# LINLCDV2.net
KiCad netlist of a schematic drawn in EAGLE
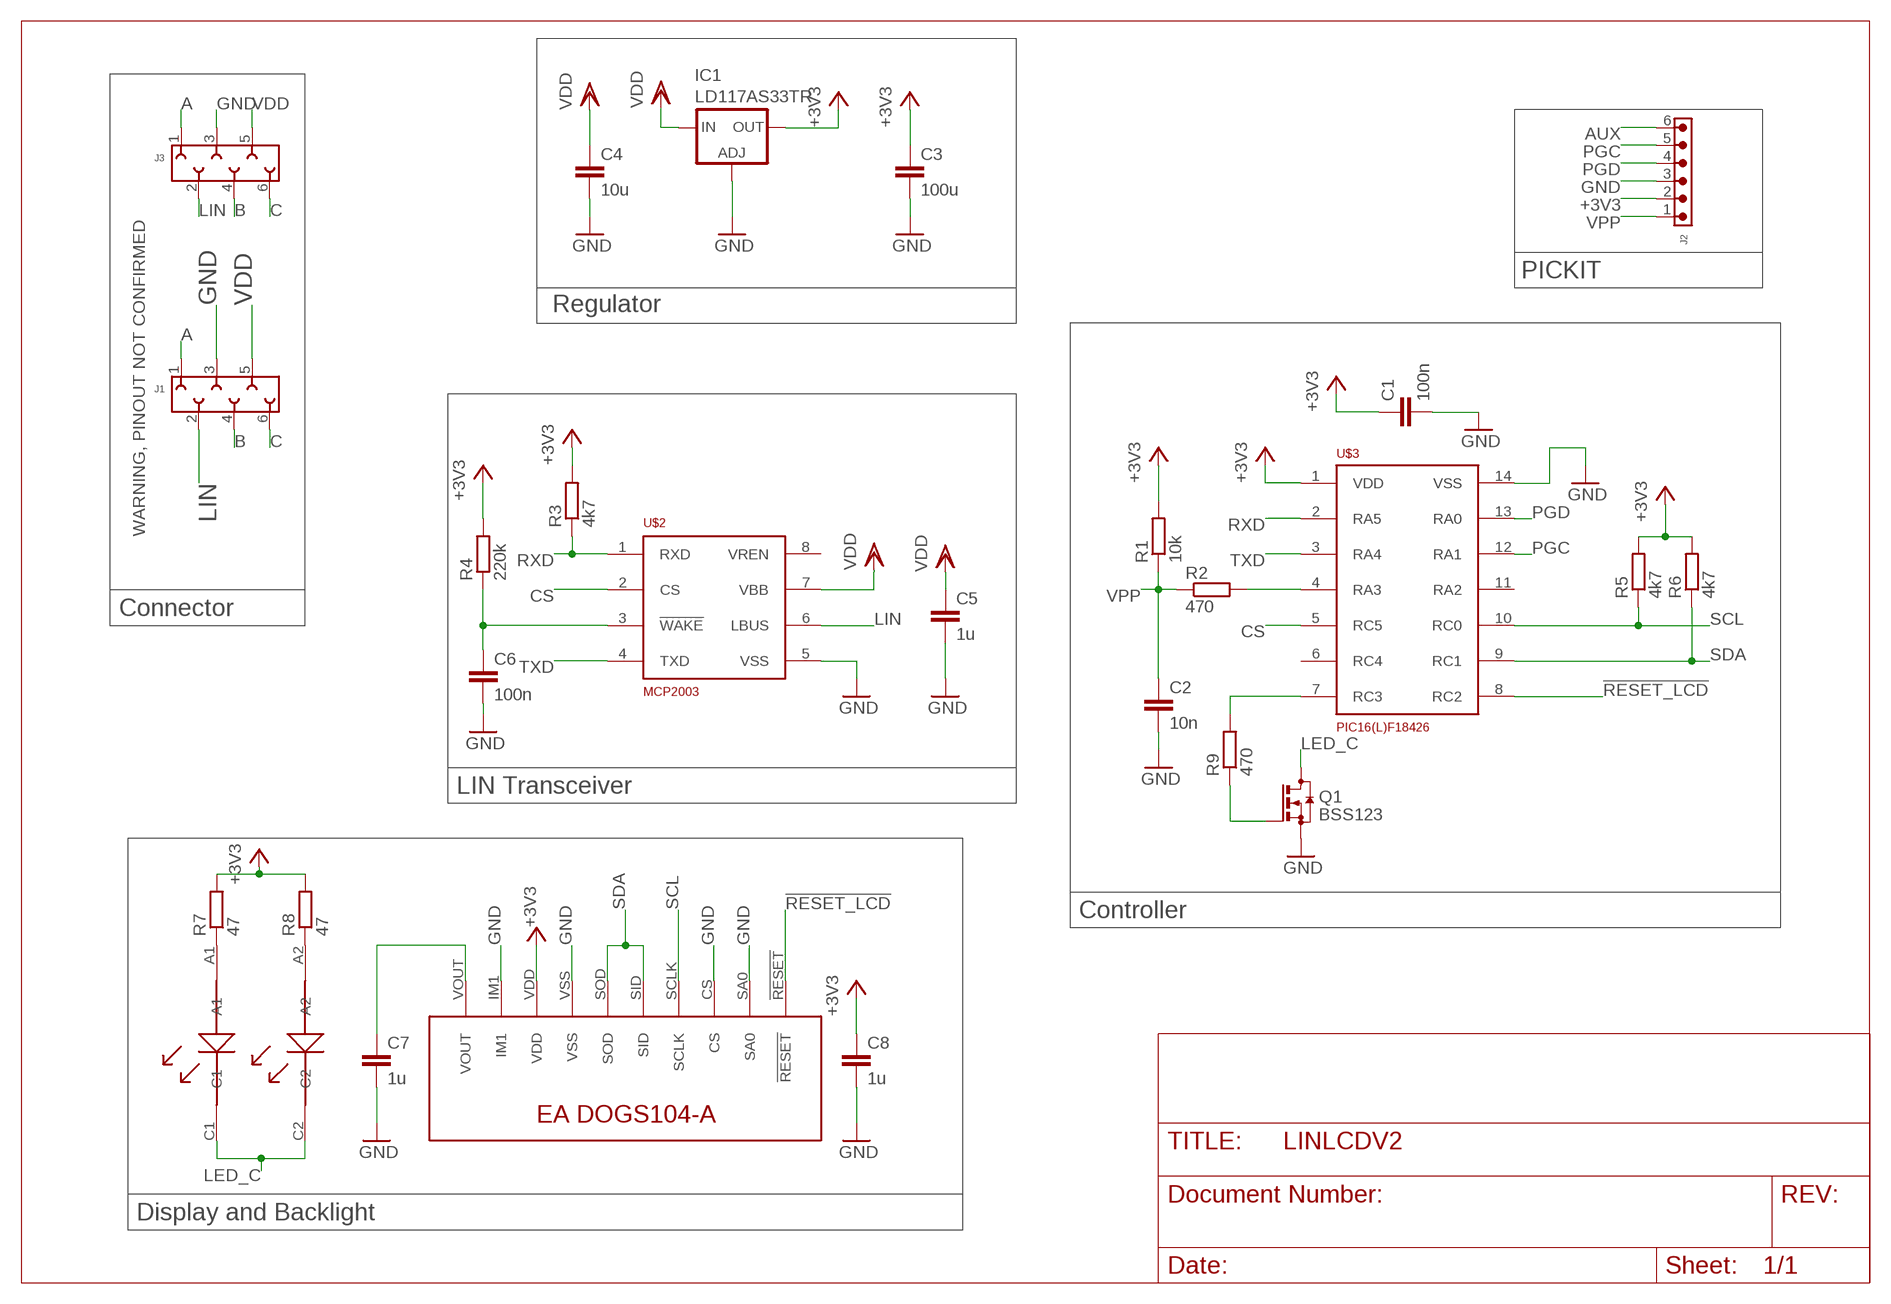
[diagram p0: schematic, sheet 1]

(export (version "E")
  (design (tool "Eeschema 10.0.6"))
  (components
    (comp (ref "C1")
      (value "100n")
      (footprint "eagle-import:C0603")
      (libsource (lib "eagle-import") (part "C-EUC0603"))
    )
    (comp (ref "C2")
      (value "10n")
      (footprint "eagle-import:C0603")
      (libsource (lib "eagle-import") (part "C-EUC0603"))
    )
    (comp (ref "C3")
      (value "100u")
      (footprint "eagle-import:C1206")
      (libsource (lib "eagle-import") (part "C-EUC1206"))
    )
    (comp (ref "C4")
      (value "10u")
      (footprint "eagle-import:C1206")
      (libsource (lib "eagle-import") (part "C-EUC1206"))
    )
    (comp (ref "C5")
      (value "1u")
      (footprint "eagle-import:C1206")
      (libsource (lib "eagle-import") (part "C-EUC1206"))
    )
    (comp (ref "C6")
      (value "100n")
      (footprint "eagle-import:C0603")
      (libsource (lib "eagle-import") (part "C-EUC0603"))
    )
    (comp (ref "C7")
      (value "1u")
      (footprint "eagle-import:C1206")
      (libsource (lib "eagle-import") (part "C-EUC1206"))
    )
    (comp (ref "C8")
      (value "1u")
      (footprint "eagle-import:C1206")
      (libsource (lib "eagle-import") (part "C-EUC1206"))
    )
    (comp (ref "IC1")
      (value "LD117AS33TR")
      (footprint "eagle-import:SOT223")
      (libsource (lib "eagle-import") (part "LD117A?S33TR"))
    )
    (comp (ref "J1")
      (value "690367280676")
      (footprint "eagle-import:690367280676")
      (libsource (lib "eagle-import") (part "690367280676"))
    )
    (comp (ref "J2")
      (value "6130XX11021_61300611021")
      (footprint "eagle-import:61300611021")
      (libsource (lib "eagle-import") (part "6130XX11021_61300611021"))
    )
    (comp (ref "J3")
      (value "690367280676")
      (footprint "eagle-import:690367280676")
      (libsource (lib "eagle-import") (part "690367280676"))
    )
    (comp (ref "Q1")
      (value "BSS123")
      (footprint "eagle-import:SOT23")
      (libsource (lib "eagle-import") (part "BSS123"))
    )
    (comp (ref "R1")
      (value "10k")
      (footprint "eagle-import:R0603")
      (libsource (lib "eagle-import") (part "R-EU_R0603"))
    )
    (comp (ref "R2")
      (value "470")
      (footprint "eagle-import:R0603")
      (libsource (lib "eagle-import") (part "R-EU_R0603"))
    )
    (comp (ref "R3")
      (value "4k7")
      (footprint "eagle-import:R0603")
      (libsource (lib "eagle-import") (part "R-EU_R0603"))
    )
    (comp (ref "R4")
      (value "220k")
      (footprint "eagle-import:R0603")
      (libsource (lib "eagle-import") (part "R-EU_R0603"))
    )
    (comp (ref "R5")
      (value "4k7")
      (footprint "eagle-import:R0603")
      (libsource (lib "eagle-import") (part "R-EU_R0603"))
    )
    (comp (ref "R6")
      (value "4k7")
      (footprint "eagle-import:R0603")
      (libsource (lib "eagle-import") (part "R-EU_R0603"))
    )
    (comp (ref "R7")
      (value "47")
      (footprint "eagle-import:R0603")
      (libsource (lib "eagle-import") (part "R-EU_R0603"))
    )
    (comp (ref "R8")
      (value "47")
      (footprint "eagle-import:R0603")
      (libsource (lib "eagle-import") (part "R-EU_R0603"))
    )
    (comp (ref "R9")
      (value "470")
      (footprint "eagle-import:R0603")
      (libsource (lib "eagle-import") (part "R-EU_R0603"))
    )
    (comp (ref "U$1")
      (value "DOGS104-A")
      (footprint "eagle-import:DOGS104-A")
      (libsource (lib "eagle-import") (part "DOGS104-A"))
    )
    (comp (ref "U$2")
      (value "MCP2003")
      (footprint "eagle-import:SO-08")
      (libsource (lib "eagle-import") (part "MCP2003"))
    )
    (comp (ref "U$3")
      (value "PIC16(L)F18426")
      (footprint "eagle-import:SO-14")
      (libsource (lib "eagle-import") (part "PIC16(L)F18426"))
    )
  )
  (nets
    (net (code "1") (name "+3V3") (class "Default")
      (node (ref "C1") (pin "1") (pinfunction "1_1") (pintype "passive"))
      (node (ref "C3") (pin "1") (pinfunction "1_1") (pintype "passive"))
      (node (ref "C8") (pin "1") (pinfunction "1_1") (pintype "passive"))
      (node (ref "IC1") (pin "4") (pinfunction "OUT_4") (pintype "passive"))
      (node (ref "J2") (pin "2") (pinfunction "2_2") (pintype "passive"))
      (node (ref "R1") (pin "2") (pinfunction "2_2") (pintype "passive"))
      (node (ref "R3") (pin "2") (pinfunction "2_2") (pintype "passive"))
      (node (ref "R4") (pin "2") (pinfunction "2_2") (pintype "passive"))
      (node (ref "R5") (pin "2") (pinfunction "2_2") (pintype "passive"))
      (node (ref "R6") (pin "2") (pinfunction "2_2") (pintype "passive"))
      (node (ref "R7") (pin "2") (pinfunction "2_2") (pintype "passive"))
      (node (ref "R8") (pin "2") (pinfunction "2_2") (pintype "passive"))
      (node (ref "U$1") (pin "VDD") (pinfunction "VDD_VDD") (pintype "bidirectional"))
      (node (ref "U$3") (pin "1") (pinfunction "VDD_1") (pintype "bidirectional"))
    )
    (net (code "2") (name "/A") (class "Default")
      (node (ref "J1") (pin "1") (pinfunction "1_1") (pintype "passive"))
      (node (ref "J3") (pin "1") (pinfunction "1_1") (pintype "passive"))
    )
    (net (code "3") (name "/AUX") (class "Default")
      (node (ref "J2") (pin "6") (pinfunction "6_6") (pintype "passive"))
    )
    (net (code "4") (name "/B") (class "Default")
      (node (ref "J1") (pin "4") (pinfunction "4_4") (pintype "passive"))
      (node (ref "J3") (pin "4") (pinfunction "4_4") (pintype "passive"))
    )
    (net (code "5") (name "/C") (class "Default")
      (node (ref "J1") (pin "6") (pinfunction "6_6") (pintype "passive"))
      (node (ref "J3") (pin "6") (pinfunction "6_6") (pintype "passive"))
    )
    (net (code "6") (name "/CS") (class "Default")
      (node (ref "U$2") (pin "2") (pinfunction "CS_2") (pintype "bidirectional"))
      (node (ref "U$3") (pin "5") (pinfunction "RC5_5") (pintype "bidirectional"))
    )
    (net (code "7") (name "/LED_C") (class "Default")
      (node (ref "Q1") (pin "3") (pinfunction "D_3") (pintype "passive"))
      (node (ref "U$1") (pin "C1") (pinfunction "C1_C1") (pintype "bidirectional"))
      (node (ref "U$1") (pin "C2") (pinfunction "C2_C2") (pintype "bidirectional"))
    )
    (net (code "8") (name "/LIN") (class "Default")
      (node (ref "J1") (pin "2") (pinfunction "2_2") (pintype "passive"))
      (node (ref "J3") (pin "2") (pinfunction "2_2") (pintype "passive"))
      (node (ref "U$2") (pin "6") (pinfunction "LBUS_6") (pintype "bidirectional"))
    )
    (net (code "9") (name "/PGC") (class "Default")
      (node (ref "J2") (pin "5") (pinfunction "5_5") (pintype "passive"))
      (node (ref "U$3") (pin "12") (pinfunction "RA1_12") (pintype "bidirectional"))
    )
    (net (code "10") (name "/PGD") (class "Default")
      (node (ref "J2") (pin "4") (pinfunction "4_4") (pintype "passive"))
      (node (ref "U$3") (pin "13") (pinfunction "RA0_13") (pintype "bidirectional"))
    )
    (net (code "11") (name "/RXD") (class "Default")
      (node (ref "R3") (pin "1") (pinfunction "1_1") (pintype "passive"))
      (node (ref "U$2") (pin "1") (pinfunction "RXD_1") (pintype "bidirectional"))
      (node (ref "U$3") (pin "2") (pinfunction "RA5_2") (pintype "bidirectional"))
    )
    (net (code "12") (name "/SCL") (class "Default")
      (node (ref "R5") (pin "1") (pinfunction "1_1") (pintype "passive"))
      (node (ref "U$1") (pin "SCLK") (pinfunction "SCLK_SCLK") (pintype "bidirectional"))
      (node (ref "U$3") (pin "10") (pinfunction "RC0_10") (pintype "bidirectional"))
    )
    (net (code "13") (name "/SDA") (class "Default")
      (node (ref "R6") (pin "1") (pinfunction "1_1") (pintype "passive"))
      (node (ref "U$1") (pin "SID") (pinfunction "SID_SID") (pintype "bidirectional"))
      (node (ref "U$1") (pin "SOD") (pinfunction "SOD_SOD") (pintype "bidirectional"))
      (node (ref "U$3") (pin "9") (pinfunction "RC1_9") (pintype "bidirectional"))
    )
    (net (code "14") (name "/TXD") (class "Default")
      (node (ref "U$2") (pin "4") (pinfunction "TXD_4") (pintype "bidirectional"))
      (node (ref "U$3") (pin "3") (pinfunction "RA4_3") (pintype "bidirectional"))
    )
    (net (code "15") (name "/VPP") (class "Default")
      (node (ref "C2") (pin "1") (pinfunction "1_1") (pintype "passive"))
      (node (ref "J2") (pin "1") (pinfunction "1_1") (pintype "passive"))
      (node (ref "R1") (pin "1") (pinfunction "1_1") (pintype "passive"))
      (node (ref "R2") (pin "1") (pinfunction "1_1") (pintype "passive"))
    )
    (net (code "16") (name "/~{RESET_LCD}") (class "Default")
      (node (ref "U$1") (pin "!RESET") (pinfunction "~{RESET}_!RESET") (pintype "bidirectional"))
      (node (ref "U$3") (pin "8") (pinfunction "RC2_8") (pintype "bidirectional"))
    )
    (net (code "17") (name "GND") (class "Default")
      (node (ref "C1") (pin "2") (pinfunction "2_2") (pintype "passive"))
      (node (ref "C2") (pin "2") (pinfunction "2_2") (pintype "passive"))
      (node (ref "C3") (pin "2") (pinfunction "2_2") (pintype "passive"))
      (node (ref "C4") (pin "2") (pinfunction "2_2") (pintype "passive"))
      (node (ref "C5") (pin "2") (pinfunction "2_2") (pintype "passive"))
      (node (ref "C6") (pin "2") (pinfunction "2_2") (pintype "passive"))
      (node (ref "C7") (pin "2") (pinfunction "2_2") (pintype "passive"))
      (node (ref "C8") (pin "2") (pinfunction "2_2") (pintype "passive"))
      (node (ref "IC1") (pin "1") (pinfunction "ADJ_1") (pintype "input"))
      (node (ref "J1") (pin "3") (pinfunction "3_3") (pintype "passive"))
      (node (ref "J2") (pin "3") (pinfunction "3_3") (pintype "passive"))
      (node (ref "J3") (pin "3") (pinfunction "3_3") (pintype "passive"))
      (node (ref "Q1") (pin "2") (pinfunction "S_2") (pintype "passive"))
      (node (ref "U$1") (pin "CS") (pinfunction "CS_CS") (pintype "bidirectional"))
      (node (ref "U$1") (pin "IM1") (pinfunction "IM1_IM1") (pintype "bidirectional"))
      (node (ref "U$1") (pin "SA0") (pinfunction "SA0_SA0") (pintype "bidirectional"))
      (node (ref "U$1") (pin "VSS") (pinfunction "VSS_VSS") (pintype "bidirectional"))
      (node (ref "U$2") (pin "5") (pinfunction "VSS_5") (pintype "bidirectional"))
      (node (ref "U$3") (pin "14") (pinfunction "VSS_14") (pintype "bidirectional"))
    )
    (net (code "18") (name "Net-(C7-Pad1)") (class "Default")
      (node (ref "C7") (pin "1") (pinfunction "1_1") (pintype "passive"))
      (node (ref "U$1") (pin "VOUT") (pinfunction "VOUT_VOUT") (pintype "bidirectional"))
    )
    (net (code "19") (name "Net-(Q1-G)") (class "Default")
      (node (ref "Q1") (pin "1") (pinfunction "G_1") (pintype "passive"))
      (node (ref "R9") (pin "1") (pinfunction "1_1") (pintype "passive"))
    )
    (net (code "20") (name "Net-(R7-Pad1)") (class "Default")
      (node (ref "R7") (pin "1") (pinfunction "1_1") (pintype "passive"))
      (node (ref "U$1") (pin "A1") (pinfunction "A1_A1") (pintype "bidirectional"))
    )
    (net (code "21") (name "Net-(R8-Pad1)") (class "Default")
      (node (ref "R8") (pin "1") (pinfunction "1_1") (pintype "passive"))
      (node (ref "U$1") (pin "A2") (pinfunction "A2_A2") (pintype "bidirectional"))
    )
    (net (code "22") (name "Net-(U$2-~{WAKE})") (class "Default")
      (node (ref "C6") (pin "1") (pinfunction "1_1") (pintype "passive"))
      (node (ref "R4") (pin "1") (pinfunction "1_1") (pintype "passive"))
      (node (ref "U$2") (pin "3") (pinfunction "~{WAKE}_3") (pintype "bidirectional"))
    )
    (net (code "23") (name "Net-(U$3-RA3)") (class "Default")
      (node (ref "R2") (pin "2") (pinfunction "2_2") (pintype "passive"))
      (node (ref "U$3") (pin "4") (pinfunction "RA3_4") (pintype "bidirectional"))
    )
    (net (code "24") (name "Net-(U$3-RC3)") (class "Default")
      (node (ref "R9") (pin "2") (pinfunction "2_2") (pintype "passive"))
      (node (ref "U$3") (pin "7") (pinfunction "RC3_7") (pintype "bidirectional"))
    )
    (net (code "25") (name "VDD") (class "Default")
      (node (ref "C4") (pin "1") (pinfunction "1_1") (pintype "passive"))
      (node (ref "C5") (pin "1") (pinfunction "1_1") (pintype "passive"))
      (node (ref "IC1") (pin "3") (pinfunction "IN_3") (pintype "input"))
      (node (ref "J1") (pin "5") (pinfunction "5_5") (pintype "passive"))
      (node (ref "J3") (pin "5") (pinfunction "5_5") (pintype "passive"))
      (node (ref "U$2") (pin "7") (pinfunction "VBB_7") (pintype "bidirectional"))
    )
    (net (code "26") (name "unconnected-(U$2-VREN-Pad8)") (class "Default")
      (node (ref "U$2") (pin "8") (pinfunction "VREN_8") (pintype "bidirectional"))
    )
    (net (code "27") (name "unconnected-(U$3-RA2-Pad11)") (class "Default")
      (node (ref "U$3") (pin "11") (pinfunction "RA2_11") (pintype "bidirectional"))
    )
    (net (code "28") (name "unconnected-(U$3-RC4-Pad6)") (class "Default")
      (node (ref "U$3") (pin "6") (pinfunction "RC4_6") (pintype "bidirectional"))
    )
  )
)
